# board.net
KiCad netlist of a schematic drawn in EAGLE
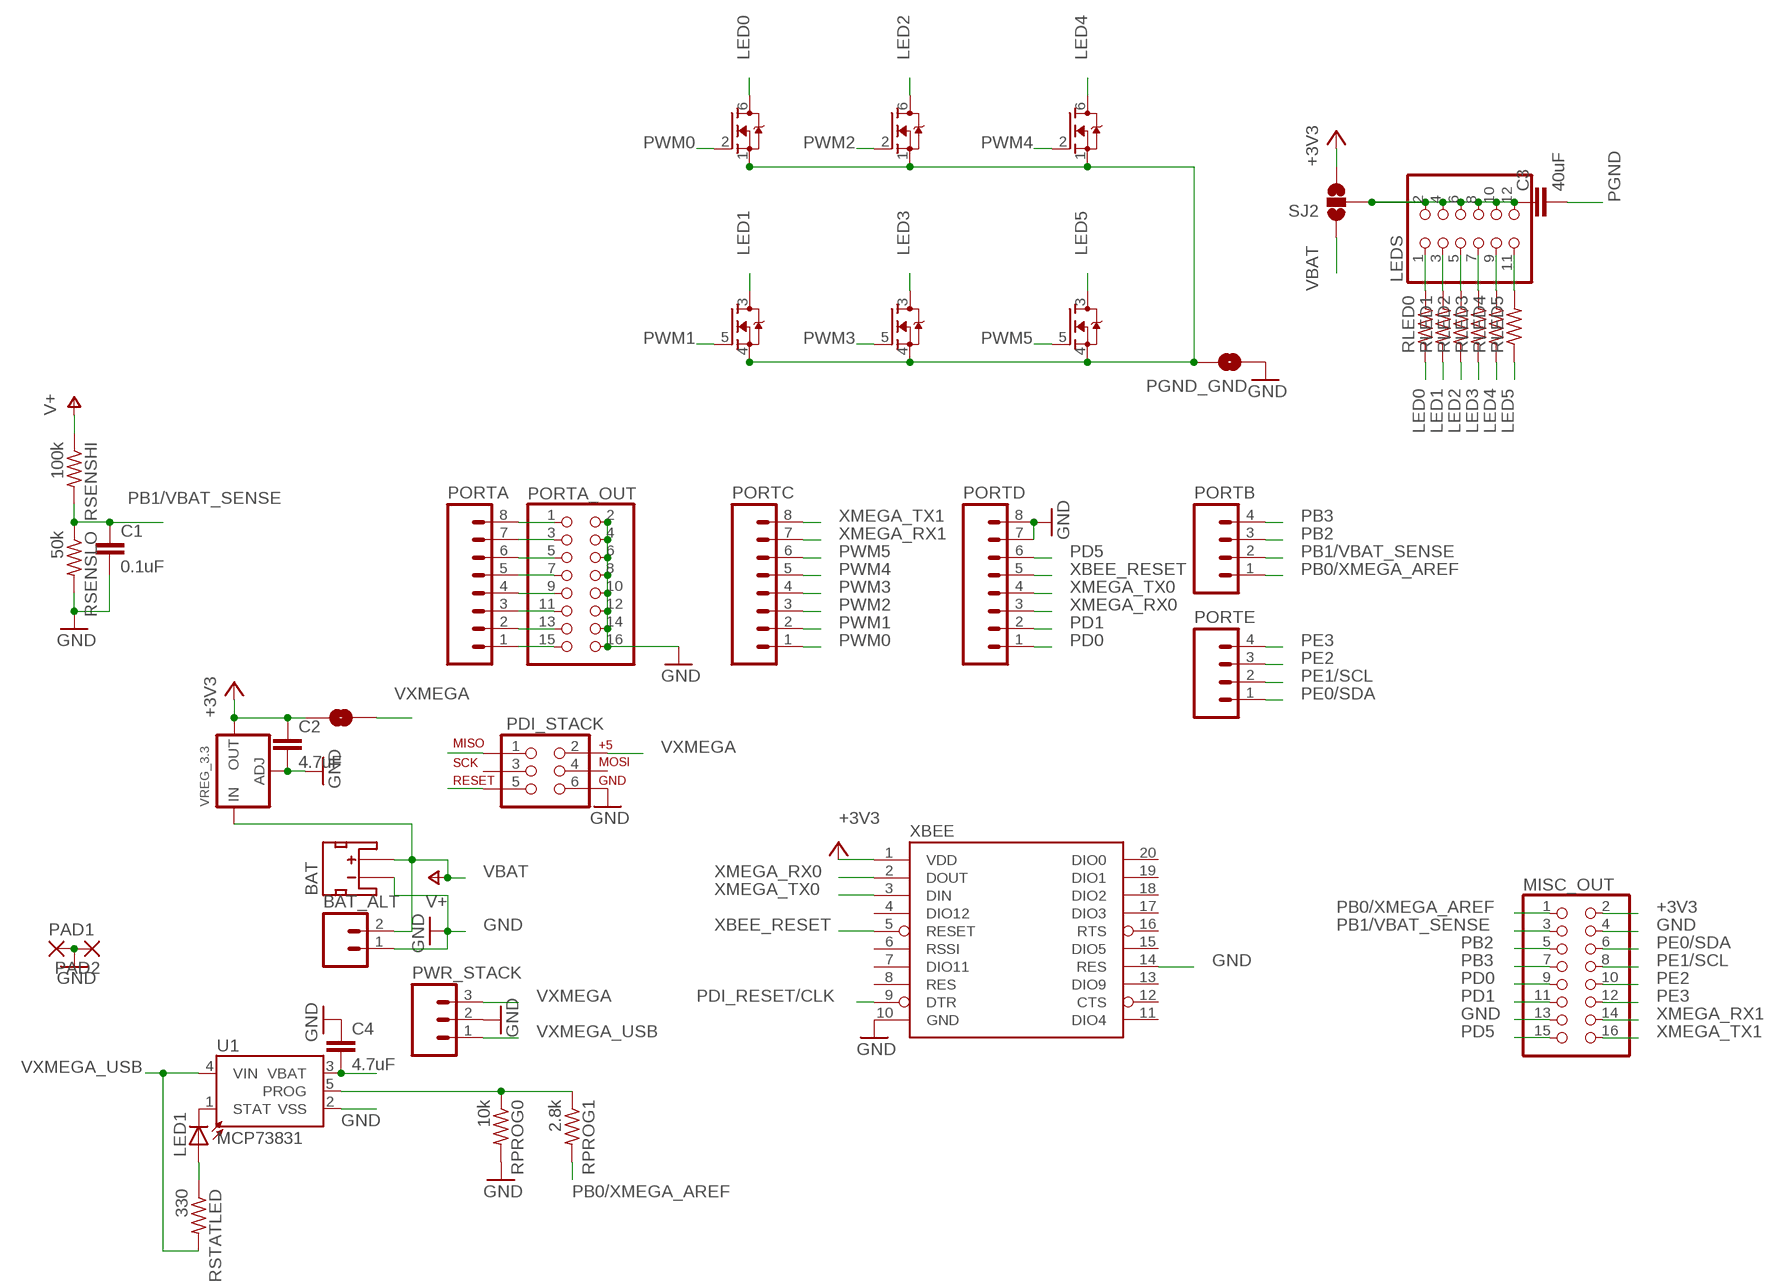
[diagram p0: schematic, sheet 1]

(export (version "E")
  (design (tool "Eeschema 10.0.6"))
  (components
    (comp (ref "+3.3V_VXMEGA")
      (value "SOLDERJUMPERTRACE")
      (footprint "eagle-import:SJ_2S-TRACE")
      (libsource (lib "eagle-import") (part "SOLDERJUMPERTRACE"))
    )
    (comp (ref "BAT")
      (value "JST_2MM_MALE")
      (footprint "eagle-import:JST-2-SMD")
      (libsource (lib "eagle-import") (part "JST_2MM_MALE"))
    )
    (comp (ref "BAT_ALT")
      (value "M02PTH")
      (footprint "eagle-import:1X02")
      (libsource (lib "eagle-import") (part "M02PTH"))
    )
    (comp (ref "C1")
      (value "0.1uF")
      (footprint "eagle-import:C0603K")
      (libsource (lib "eagle-import") (part "C-EUC0603K"))
    )
    (comp (ref "C2")
      (value "4.7uF")
      (footprint "eagle-import:C0805K")
      (libsource (lib "eagle-import") (part "C-EUC0805K"))
    )
    (comp (ref "C3")
      (value "40uF")
      (footprint "eagle-import:C1210")
      (libsource (lib "eagle-import") (part "C-EUC1210"))
    )
    (comp (ref "C4")
      (value "4.7uF")
      (footprint "eagle-import:C0805")
      (libsource (lib "eagle-import") (part "C-EUC0805"))
    )
    (comp (ref "DRV0")
      (value "MOSFET-N_DUAL")
      (footprint "eagle-import:SOT363")
      (libsource (lib "eagle-import") (part "MOSFET-N_DUAL"))
    )
    (comp (ref "DRV1")
      (value "MOSFET-N_DUAL")
      (footprint "eagle-import:SOT363")
      (libsource (lib "eagle-import") (part "MOSFET-N_DUAL"))
    )
    (comp (ref "DRV2")
      (value "MOSFET-N_DUAL")
      (footprint "eagle-import:SOT363")
      (libsource (lib "eagle-import") (part "MOSFET-N_DUAL"))
    )
    (comp (ref "LED1")
      (value "LEDCHIP-LED0603")
      (footprint "eagle-import:CHIP-LED0603")
      (libsource (lib "eagle-import") (part "LEDCHIP-LED0603"))
    )
    (comp (ref "LEDS")
      (value "PINHD-2X6/90")
      (footprint "eagle-import:2X06_90")
      (libsource (lib "eagle-import") (part "PINHD-2X6/90"))
    )
    (comp (ref "MISC_OUT")
      (value "PINHD-2X8/90")
      (footprint "eagle-import:2X08_90")
      (libsource (lib "eagle-import") (part "PINHD-2X8/90"))
    )
    (comp (ref "PAD1")
      (value "3,81/1,4")
      (footprint "eagle-import:3,81_1,4")
      (libsource (lib "eagle-import") (part "3,81/1,4"))
    )
    (comp (ref "PAD2")
      (value "3,81/1,4")
      (footprint "eagle-import:3,81_1,4")
      (libsource (lib "eagle-import") (part "3,81/1,4"))
    )
    (comp (ref "PDI_STACK")
      (value "AVR_SPI_PRG_6NS")
      (footprint "eagle-import:2X3-NS")
      (libsource (lib "eagle-import") (part "AVR_SPI_PRG_6NS"))
    )
    (comp (ref "PGND_GND")
      (value "SOLDERJUMPERTRACE")
      (footprint "eagle-import:SJ_2S-TRACE")
      (libsource (lib "eagle-import") (part "SOLDERJUMPERTRACE"))
    )
    (comp (ref "PORTA")
      (value "M081X08")
      (footprint "eagle-import:1X08")
      (libsource (lib "eagle-import") (part "M081X08"))
    )
    (comp (ref "PORTA_OUT")
      (value "PINHD-2X8")
      (footprint "eagle-import:2X08")
      (libsource (lib "eagle-import") (part "PINHD-2X8"))
    )
    (comp (ref "PORTB")
      (value "M04PTH")
      (footprint "eagle-import:1X04")
      (libsource (lib "eagle-import") (part "M04PTH"))
    )
    (comp (ref "PORTC")
      (value "M081X08")
      (footprint "eagle-import:1X08")
      (libsource (lib "eagle-import") (part "M081X08"))
    )
    (comp (ref "PORTD")
      (value "M081X08")
      (footprint "eagle-import:1X08")
      (libsource (lib "eagle-import") (part "M081X08"))
    )
    (comp (ref "PORTE")
      (value "M04PTH")
      (footprint "eagle-import:1X04")
      (libsource (lib "eagle-import") (part "M04PTH"))
    )
    (comp (ref "PWR_STACK")
      (value "M03PTH")
      (footprint "eagle-import:1X03")
      (libsource (lib "eagle-import") (part "M03PTH"))
    )
    (comp (ref "RLED0")
      (value "R-US_R0805")
      (footprint "eagle-import:R0805")
      (libsource (lib "eagle-import") (part "resistor_R-US_R0805"))
    )
    (comp (ref "RLED1")
      (value "R-US_R0805")
      (footprint "eagle-import:R0805")
      (libsource (lib "eagle-import") (part "resistor_R-US_R0805"))
    )
    (comp (ref "RLED2")
      (value "R-US_R0805")
      (footprint "eagle-import:R0805")
      (libsource (lib "eagle-import") (part "resistor_R-US_R0805"))
    )
    (comp (ref "RLED3")
      (value "R-US_R0805")
      (footprint "eagle-import:R0805")
      (libsource (lib "eagle-import") (part "resistor_R-US_R0805"))
    )
    (comp (ref "RLED4")
      (value "R-US_R0805")
      (footprint "eagle-import:R0805")
      (libsource (lib "eagle-import") (part "resistor_R-US_R0805"))
    )
    (comp (ref "RLED5")
      (value "R-US_R0805")
      (footprint "eagle-import:R0805")
      (libsource (lib "eagle-import") (part "resistor_R-US_R0805"))
    )
    (comp (ref "RPROG0")
      (value "10k")
      (footprint "eagle-import:R0603")
      (libsource (lib "eagle-import") (part "R-US_R0603"))
    )
    (comp (ref "RPROG1")
      (value "2.8k")
      (footprint "eagle-import:R0603")
      (libsource (lib "eagle-import") (part "R-US_R0603"))
    )
    (comp (ref "RSENSHI")
      (value "100k")
      (footprint "eagle-import:R0603")
      (libsource (lib "eagle-import") (part "R-US_R0603"))
    )
    (comp (ref "RSENSLO")
      (value "50k")
      (footprint "eagle-import:R0603")
      (libsource (lib "eagle-import") (part "R-US_R0603"))
    )
    (comp (ref "RSTATLED")
      (value "330")
      (footprint "eagle-import:R0603")
      (libsource (lib "eagle-import") (part "R-US_R0603"))
    )
    (comp (ref "SJ2")
      (value "SOLDERJUMPER_2WAY-OLDT")
      (footprint "eagle-import:SJ_2")
      (libsource (lib "eagle-import") (part "SOLDERJUMPER_2WAY-OLDT"))
    )
    (comp (ref "U1")
      (value "MCP73831")
      (footprint "eagle-import:SOT23-5")
      (libsource (lib "eagle-import") (part "MCP73831"))
    )
    (comp (ref "VREG_3.3")
      (value "LM1117SOT223-WAVE")
      (footprint "eagle-import:SOT223-W")
      (libsource (lib "eagle-import") (part "LM1117SOT223-WAVE"))
    )
    (comp (ref "XBEE")
      (value "XBEE-1B2")
      (footprint "eagle-import:XBEE-SILK")
      (libsource (lib "eagle-import") (part "XBEE-1B2"))
    )
  )
  (nets
    (net (code "1") (name "+3V3") (class "Default")
      (node (ref "+3.3V_VXMEGA") (pin "1") (pinfunction "1_1") (pintype "passive"))
      (node (ref "C2") (pin "1") (pinfunction "1_1") (pintype "passive"))
      (node (ref "MISC_OUT") (pin "2") (pinfunction "2_2") (pintype "passive"))
      (node (ref "SJ2") (pin "3") (pinfunction "3_3") (pintype "passive"))
      (node (ref "VREG_3.3") (pin "2") (pinfunction "OUT_2") (pintype "passive"))
      (node (ref "XBEE") (pin "1") (pinfunction "VDD_1") (pintype "power_in"))
    )
    (net (code "2") (name "/LED0") (class "Default")
      (node (ref "DRV0") (pin "6") (pinfunction "D_6") (pintype "bidirectional"))
      (node (ref "RLED0") (pin "1") (pinfunction "1_1") (pintype "passive"))
    )
    (net (code "3") (name "/LED1") (class "Default")
      (node (ref "DRV0") (pin "3") (pinfunction "D_3") (pintype "bidirectional"))
      (node (ref "RLED1") (pin "1") (pinfunction "1_1") (pintype "passive"))
    )
    (net (code "4") (name "/LED2") (class "Default")
      (node (ref "DRV1") (pin "6") (pinfunction "D_6") (pintype "bidirectional"))
      (node (ref "RLED2") (pin "1") (pinfunction "1_1") (pintype "passive"))
    )
    (net (code "5") (name "/LED3") (class "Default")
      (node (ref "DRV1") (pin "3") (pinfunction "D_3") (pintype "bidirectional"))
      (node (ref "RLED3") (pin "1") (pinfunction "1_1") (pintype "passive"))
    )
    (net (code "6") (name "/LED4") (class "Default")
      (node (ref "DRV2") (pin "6") (pinfunction "D_6") (pintype "bidirectional"))
      (node (ref "RLED4") (pin "1") (pinfunction "1_1") (pintype "passive"))
    )
    (net (code "7") (name "/LED5") (class "Default")
      (node (ref "DRV2") (pin "3") (pinfunction "D_3") (pintype "bidirectional"))
      (node (ref "RLED5") (pin "1") (pinfunction "1_1") (pintype "passive"))
    )
    (net (code "8") (name "/PB0{slash}XMEGA_AREF") (class "Default")
      (node (ref "MISC_OUT") (pin "1") (pinfunction "1_1") (pintype "passive"))
      (node (ref "PORTB") (pin "1") (pinfunction "1_1") (pintype "passive"))
      (node (ref "RPROG1") (pin "2") (pinfunction "2_2") (pintype "passive"))
    )
    (net (code "9") (name "/PB1{slash}VBAT_SENSE") (class "Default")
      (node (ref "C1") (pin "1") (pinfunction "1_1") (pintype "passive"))
      (node (ref "MISC_OUT") (pin "3") (pinfunction "3_3") (pintype "passive"))
      (node (ref "PORTB") (pin "2") (pinfunction "2_2") (pintype "passive"))
      (node (ref "RSENSHI") (pin "2") (pinfunction "2_2") (pintype "passive"))
      (node (ref "RSENSLO") (pin "1") (pinfunction "1_1") (pintype "passive"))
    )
    (net (code "10") (name "/PB2") (class "Default")
      (node (ref "MISC_OUT") (pin "5") (pinfunction "5_5") (pintype "passive"))
      (node (ref "PORTB") (pin "3") (pinfunction "3_3") (pintype "passive"))
    )
    (net (code "11") (name "/PB3") (class "Default")
      (node (ref "MISC_OUT") (pin "7") (pinfunction "7_7") (pintype "passive"))
      (node (ref "PORTB") (pin "4") (pinfunction "4_4") (pintype "passive"))
    )
    (net (code "12") (name "/PD0") (class "Default")
      (node (ref "MISC_OUT") (pin "9") (pinfunction "9_9") (pintype "passive"))
      (node (ref "PORTD") (pin "1") (pinfunction "1_1") (pintype "passive"))
    )
    (net (code "13") (name "/PD1") (class "Default")
      (node (ref "MISC_OUT") (pin "11") (pinfunction "11_11") (pintype "passive"))
      (node (ref "PORTD") (pin "2") (pinfunction "2_2") (pintype "passive"))
    )
    (net (code "14") (name "/PD5") (class "Default")
      (node (ref "MISC_OUT") (pin "15") (pinfunction "15_15") (pintype "passive"))
      (node (ref "PORTD") (pin "6") (pinfunction "6_6") (pintype "passive"))
    )
    (net (code "15") (name "/PDI_RESET{slash}CLK") (class "Default")
      (node (ref "PDI_STACK") (pin "5") (pinfunction "5_5") (pintype "passive"))
      (node (ref "XBEE") (pin "9") (pinfunction "DTR_9") (pintype "bidirectional"))
    )
    (net (code "16") (name "/PE0{slash}SDA") (class "Default")
      (node (ref "MISC_OUT") (pin "6") (pinfunction "6_6") (pintype "passive"))
      (node (ref "PORTE") (pin "1") (pinfunction "1_1") (pintype "passive"))
    )
    (net (code "17") (name "/PE1{slash}SCL") (class "Default")
      (node (ref "MISC_OUT") (pin "8") (pinfunction "8_8") (pintype "passive"))
      (node (ref "PORTE") (pin "2") (pinfunction "2_2") (pintype "passive"))
    )
    (net (code "18") (name "/PE2") (class "Default")
      (node (ref "MISC_OUT") (pin "10") (pinfunction "10_10") (pintype "passive"))
      (node (ref "PORTE") (pin "3") (pinfunction "3_3") (pintype "passive"))
    )
    (net (code "19") (name "/PE3") (class "Default")
      (node (ref "MISC_OUT") (pin "12") (pinfunction "12_12") (pintype "passive"))
      (node (ref "PORTE") (pin "4") (pinfunction "4_4") (pintype "passive"))
    )
    (net (code "20") (name "/PGND") (class "Default")
      (node (ref "C3") (pin "2") (pinfunction "2_2") (pintype "passive"))
      (node (ref "DRV0") (pin "1") (pinfunction "S_1") (pintype "bidirectional"))
      (node (ref "DRV0") (pin "4") (pinfunction "S_4") (pintype "bidirectional"))
      (node (ref "DRV1") (pin "1") (pinfunction "S_1") (pintype "bidirectional"))
      (node (ref "DRV1") (pin "4") (pinfunction "S_4") (pintype "bidirectional"))
      (node (ref "DRV2") (pin "1") (pinfunction "S_1") (pintype "bidirectional"))
      (node (ref "DRV2") (pin "4") (pinfunction "S_4") (pintype "bidirectional"))
      (node (ref "PGND_GND") (pin "2") (pinfunction "2_2") (pintype "passive"))
    )
    (net (code "21") (name "/PWM0") (class "Default")
      (node (ref "DRV0") (pin "2") (pinfunction "G_2") (pintype "bidirectional"))
      (node (ref "PORTC") (pin "1") (pinfunction "1_1") (pintype "passive"))
    )
    (net (code "22") (name "/PWM1") (class "Default")
      (node (ref "DRV0") (pin "5") (pinfunction "G_5") (pintype "bidirectional"))
      (node (ref "PORTC") (pin "2") (pinfunction "2_2") (pintype "passive"))
    )
    (net (code "23") (name "/PWM2") (class "Default")
      (node (ref "DRV1") (pin "2") (pinfunction "G_2") (pintype "bidirectional"))
      (node (ref "PORTC") (pin "3") (pinfunction "3_3") (pintype "passive"))
    )
    (net (code "24") (name "/PWM3") (class "Default")
      (node (ref "DRV1") (pin "5") (pinfunction "G_5") (pintype "bidirectional"))
      (node (ref "PORTC") (pin "4") (pinfunction "4_4") (pintype "passive"))
    )
    (net (code "25") (name "/PWM4") (class "Default")
      (node (ref "DRV2") (pin "2") (pinfunction "G_2") (pintype "bidirectional"))
      (node (ref "PORTC") (pin "5") (pinfunction "5_5") (pintype "passive"))
    )
    (net (code "26") (name "/PWM5") (class "Default")
      (node (ref "DRV2") (pin "5") (pinfunction "G_5") (pintype "bidirectional"))
      (node (ref "PORTC") (pin "6") (pinfunction "6_6") (pintype "passive"))
    )
    (net (code "27") (name "/VXMEGA") (class "Default")
      (node (ref "+3.3V_VXMEGA") (pin "2") (pinfunction "2_2") (pintype "passive"))
      (node (ref "PDI_STACK") (pin "2") (pinfunction "2_2") (pintype "passive"))
      (node (ref "PWR_STACK") (pin "3") (pinfunction "3_3") (pintype "passive"))
    )
    (net (code "28") (name "/VXMEGA_USB") (class "Default")
      (node (ref "PWR_STACK") (pin "1") (pinfunction "1_1") (pintype "passive"))
      (node (ref "RSTATLED") (pin "2") (pinfunction "2_2") (pintype "passive"))
      (node (ref "U1") (pin "4") (pinfunction "VIN_4") (pintype "power_in"))
    )
    (net (code "29") (name "/XBEE_RESET") (class "Default")
      (node (ref "PORTD") (pin "5") (pinfunction "5_5") (pintype "passive"))
      (node (ref "XBEE") (pin "5") (pinfunction "RESET_5") (pintype "input"))
    )
    (net (code "30") (name "/XMEGA_RX0") (class "Default")
      (node (ref "PORTD") (pin "3") (pinfunction "3_3") (pintype "passive"))
      (node (ref "XBEE") (pin "2") (pinfunction "DOUT_2") (pintype "output"))
    )
    (net (code "31") (name "/XMEGA_RX1") (class "Default")
      (node (ref "MISC_OUT") (pin "14") (pinfunction "14_14") (pintype "passive"))
      (node (ref "PORTC") (pin "7") (pinfunction "7_7") (pintype "passive"))
    )
    (net (code "32") (name "/XMEGA_TX0") (class "Default")
      (node (ref "PORTD") (pin "4") (pinfunction "4_4") (pintype "passive"))
      (node (ref "XBEE") (pin "3") (pinfunction "DIN_3") (pintype "input"))
    )
    (net (code "33") (name "/XMEGA_TX1") (class "Default")
      (node (ref "MISC_OUT") (pin "16") (pinfunction "16_16") (pintype "passive"))
      (node (ref "PORTC") (pin "8") (pinfunction "8_8") (pintype "passive"))
    )
    (net (code "34") (name "GND") (class "Default")
      (node (ref "BAT") (pin "1") (pinfunction "-_1") (pintype "bidirectional"))
      (node (ref "BAT_ALT") (pin "1") (pinfunction "1_1") (pintype "passive"))
      (node (ref "C1") (pin "2") (pinfunction "2_2") (pintype "passive"))
      (node (ref "C2") (pin "2") (pinfunction "2_2") (pintype "passive"))
      (node (ref "C4") (pin "1") (pinfunction "1_1") (pintype "passive"))
      (node (ref "MISC_OUT") (pin "13") (pinfunction "13_13") (pintype "passive"))
      (node (ref "MISC_OUT") (pin "4") (pinfunction "4_4") (pintype "passive"))
      (node (ref "PAD1") (pin "1") (pinfunction "P_1") (pintype "passive"))
      (node (ref "PAD2") (pin "1") (pinfunction "P_1") (pintype "passive"))
      (node (ref "PDI_STACK") (pin "6") (pinfunction "6_6") (pintype "passive"))
      (node (ref "PGND_GND") (pin "1") (pinfunction "1_1") (pintype "passive"))
      (node (ref "PORTA_OUT") (pin "10") (pinfunction "10_10") (pintype "passive"))
      (node (ref "PORTA_OUT") (pin "12") (pinfunction "12_12") (pintype "passive"))
      (node (ref "PORTA_OUT") (pin "14") (pinfunction "14_14") (pintype "passive"))
      (node (ref "PORTA_OUT") (pin "16") (pinfunction "16_16") (pintype "passive"))
      (node (ref "PORTA_OUT") (pin "2") (pinfunction "2_2") (pintype "passive"))
      (node (ref "PORTA_OUT") (pin "4") (pinfunction "4_4") (pintype "passive"))
      (node (ref "PORTA_OUT") (pin "6") (pinfunction "6_6") (pintype "passive"))
      (node (ref "PORTA_OUT") (pin "8") (pinfunction "8_8") (pintype "passive"))
      (node (ref "PORTD") (pin "7") (pinfunction "7_7") (pintype "passive"))
      (node (ref "PORTD") (pin "8") (pinfunction "8_8") (pintype "passive"))
      (node (ref "PWR_STACK") (pin "2") (pinfunction "2_2") (pintype "passive"))
      (node (ref "RPROG0") (pin "2") (pinfunction "2_2") (pintype "passive"))
      (node (ref "RSENSLO") (pin "2") (pinfunction "2_2") (pintype "passive"))
      (node (ref "U1") (pin "2") (pinfunction "VSS_2") (pintype "power_in"))
      (node (ref "VREG_3.3") (pin "1") (pinfunction "ADJ_1") (pintype "input"))
      (node (ref "XBEE") (pin "10") (pinfunction "GND_10") (pintype "power_in"))
      (node (ref "XBEE") (pin "14") (pinfunction "RES_14") (pintype "bidirectional"))
    )
    (net (code "35") (name "Net-(C3-Pad1)") (class "Default")
      (node (ref "C3") (pin "1") (pinfunction "1_1") (pintype "passive"))
      (node (ref "LEDS") (pin "10") (pinfunction "10_10") (pintype "passive"))
      (node (ref "LEDS") (pin "12") (pinfunction "12_12") (pintype "passive"))
      (node (ref "LEDS") (pin "2") (pinfunction "2_2") (pintype "passive"))
      (node (ref "LEDS") (pin "4") (pinfunction "4_4") (pintype "passive"))
      (node (ref "LEDS") (pin "6") (pinfunction "6_6") (pintype "passive"))
      (node (ref "LEDS") (pin "8") (pinfunction "8_8") (pintype "passive"))
      (node (ref "SJ2") (pin "2") (pinfunction "2_2") (pintype "passive"))
    )
    (net (code "36") (name "Net-(LED1-PadA)") (class "Default")
      (node (ref "LED1") (pin "A") (pinfunction "A_A") (pintype "passive"))
      (node (ref "RSTATLED") (pin "1") (pinfunction "1_1") (pintype "passive"))
    )
    (net (code "37") (name "Net-(LEDS-Pad1)") (class "Default")
      (node (ref "LEDS") (pin "1") (pinfunction "1_1") (pintype "passive"))
      (node (ref "RLED0") (pin "2") (pinfunction "2_2") (pintype "passive"))
    )
    (net (code "38") (name "Net-(LEDS-Pad3)") (class "Default")
      (node (ref "LEDS") (pin "3") (pinfunction "3_3") (pintype "passive"))
      (node (ref "RLED1") (pin "2") (pinfunction "2_2") (pintype "passive"))
    )
    (net (code "39") (name "Net-(LEDS-Pad5)") (class "Default")
      (node (ref "LEDS") (pin "5") (pinfunction "5_5") (pintype "passive"))
      (node (ref "RLED2") (pin "2") (pinfunction "2_2") (pintype "passive"))
    )
    (net (code "40") (name "Net-(LEDS-Pad7)") (class "Default")
      (node (ref "LEDS") (pin "7") (pinfunction "7_7") (pintype "passive"))
      (node (ref "RLED3") (pin "2") (pinfunction "2_2") (pintype "passive"))
    )
    (net (code "41") (name "Net-(LEDS-Pad9)") (class "Default")
      (node (ref "LEDS") (pin "9") (pinfunction "9_9") (pintype "passive"))
      (node (ref "RLED4") (pin "2") (pinfunction "2_2") (pintype "passive"))
    )
    (net (code "42") (name "Net-(LEDS-Pad11)") (class "Default")
      (node (ref "LEDS") (pin "11") (pinfunction "11_11") (pintype "passive"))
      (node (ref "RLED5") (pin "2") (pinfunction "2_2") (pintype "passive"))
    )
    (net (code "43") (name "Net-(PORTA-Pad1)") (class "Default")
      (node (ref "PORTA") (pin "1") (pinfunction "1_1") (pintype "passive"))
      (node (ref "PORTA_OUT") (pin "15") (pinfunction "15_15") (pintype "passive"))
    )
    (net (code "44") (name "Net-(PORTA-Pad2)") (class "Default")
      (node (ref "PORTA") (pin "2") (pinfunction "2_2") (pintype "passive"))
      (node (ref "PORTA_OUT") (pin "13") (pinfunction "13_13") (pintype "passive"))
    )
    (net (code "45") (name "Net-(PORTA-Pad3)") (class "Default")
      (node (ref "PORTA") (pin "3") (pinfunction "3_3") (pintype "passive"))
      (node (ref "PORTA_OUT") (pin "11") (pinfunction "11_11") (pintype "passive"))
    )
    (net (code "46") (name "Net-(PORTA-Pad4)") (class "Default")
      (node (ref "PORTA") (pin "4") (pinfunction "4_4") (pintype "passive"))
      (node (ref "PORTA_OUT") (pin "9") (pinfunction "9_9") (pintype "passive"))
    )
    (net (code "47") (name "Net-(PORTA-Pad5)") (class "Default")
      (node (ref "PORTA") (pin "5") (pinfunction "5_5") (pintype "passive"))
      (node (ref "PORTA_OUT") (pin "7") (pinfunction "7_7") (pintype "passive"))
    )
    (net (code "48") (name "Net-(PORTA-Pad6)") (class "Default")
      (node (ref "PORTA") (pin "6") (pinfunction "6_6") (pintype "passive"))
      (node (ref "PORTA_OUT") (pin "5") (pinfunction "5_5") (pintype "passive"))
    )
    (net (code "49") (name "Net-(PORTA-Pad7)") (class "Default")
      (node (ref "PORTA") (pin "7") (pinfunction "7_7") (pintype "passive"))
      (node (ref "PORTA_OUT") (pin "3") (pinfunction "3_3") (pintype "passive"))
    )
    (net (code "50") (name "Net-(PORTA-Pad8)") (class "Default")
      (node (ref "PORTA") (pin "8") (pinfunction "8_8") (pintype "passive"))
      (node (ref "PORTA_OUT") (pin "1") (pinfunction "1_1") (pintype "passive"))
    )
    (net (code "51") (name "Net-(U1-PROG)") (class "Default")
      (node (ref "RPROG0") (pin "1") (pinfunction "1_1") (pintype "passive"))
      (node (ref "RPROG1") (pin "1") (pinfunction "1_1") (pintype "passive"))
      (node (ref "U1") (pin "5") (pinfunction "PROG_5") (pintype "input"))
    )
    (net (code "52") (name "Net-(U1-STAT)") (class "Default")
      (node (ref "LED1") (pin "C") (pinfunction "C_C") (pintype "passive"))
      (node (ref "U1") (pin "1") (pinfunction "STAT_1") (pintype "output"))
    )
    (net (code "53") (name "V+") (class "Default")
      (node (ref "BAT") (pin "2") (pinfunction "+_2") (pintype "bidirectional"))
      (node (ref "BAT_ALT") (pin "2") (pinfunction "2_2") (pintype "passive"))
      (node (ref "C4") (pin "2") (pinfunction "2_2") (pintype "passive"))
      (node (ref "RSENSHI") (pin "1") (pinfunction "1_1") (pintype "passive"))
      (node (ref "SJ2") (pin "1") (pinfunction "1_1") (pintype "passive"))
      (node (ref "U1") (pin "3") (pinfunction "VBAT_3") (pintype "power_in"))
      (node (ref "VREG_3.3") (pin "3") (pinfunction "IN_3") (pintype "input"))
    )
    (net (code "54") (name "unconnected-(BAT-PAD1-PadNC1)") (class "Default")
      (node (ref "BAT") (pin "NC1") (pinfunction "PAD1_NC1") (pintype "bidirectional"))
    )
    (net (code "55") (name "unconnected-(BAT-PAD2-PadNC2)") (class "Default")
      (node (ref "BAT") (pin "NC2") (pinfunction "PAD2_NC2") (pintype "bidirectional"))
    )
    (net (code "56") (name "unconnected-(PDI_STACK-Pad1)") (class "Default")
      (node (ref "PDI_STACK") (pin "1") (pinfunction "1_1") (pintype "passive"))
    )
    (net (code "57") (name "unconnected-(PDI_STACK-Pad3)") (class "Default")
      (node (ref "PDI_STACK") (pin "3") (pinfunction "3_3") (pintype "passive"))
    )
    (net (code "58") (name "unconnected-(PDI_STACK-Pad4)") (class "Default")
      (node (ref "PDI_STACK") (pin "4") (pinfunction "4_4") (pintype "passive"))
    )
    (net (code "59") (name "unconnected-(XBEE-CTS-Pad12)") (class "Default")
      (node (ref "XBEE") (pin "12") (pinfunction "CTS_12") (pintype "output"))
    )
    (net (code "60") (name "unconnected-(XBEE-DIO0-Pad20)") (class "Default")
      (node (ref "XBEE") (pin "20") (pinfunction "DIO0_20") (pintype "bidirectional"))
    )
    (net (code "61") (name "unconnected-(XBEE-DIO1-Pad19)") (class "Default")
      (node (ref "XBEE") (pin "19") (pinfunction "DIO1_19") (pintype "bidirectional"))
    )
    (net (code "62") (name "unconnected-(XBEE-DIO2-Pad18)") (class "Default")
      (node (ref "XBEE") (pin "18") (pinfunction "DIO2_18") (pintype "bidirectional"))
    )
    (net (code "63") (name "unconnected-(XBEE-DIO3-Pad17)") (class "Default")
      (node (ref "XBEE") (pin "17") (pinfunction "DIO3_17") (pintype "bidirectional"))
    )
    (net (code "64") (name "unconnected-(XBEE-DIO4-Pad11)") (class "Default")
      (node (ref "XBEE") (pin "11") (pinfunction "DIO4_11") (pintype "bidirectional"))
    )
    (net (code "65") (name "unconnected-(XBEE-DIO5-Pad15)") (class "Default")
      (node (ref "XBEE") (pin "15") (pinfunction "DIO5_15") (pintype "bidirectional"))
    )
    (net (code "66") (name "unconnected-(XBEE-DIO9-Pad13)") (class "Default")
      (node (ref "XBEE") (pin "13") (pinfunction "DIO9_13") (pintype "bidirectional"))
    )
    (net (code "67") (name "unconnected-(XBEE-DIO11-Pad7)") (class "Default")
      (node (ref "XBEE") (pin "7") (pinfunction "DIO11_7") (pintype "bidirectional"))
    )
    (net (code "68") (name "unconnected-(XBEE-DIO12-Pad4)") (class "Default")
      (node (ref "XBEE") (pin "4") (pinfunction "DIO12_4") (pintype "bidirectional"))
    )
    (net (code "69") (name "unconnected-(XBEE-RES-Pad8)") (class "Default")
      (node (ref "XBEE") (pin "8") (pinfunction "RES_8") (pintype "bidirectional"))
    )
    (net (code "70") (name "unconnected-(XBEE-RSSI-Pad6)") (class "Default")
      (node (ref "XBEE") (pin "6") (pinfunction "RSSI_6") (pintype "bidirectional"))
    )
    (net (code "71") (name "unconnected-(XBEE-RTS-Pad16)") (class "Default")
      (node (ref "XBEE") (pin "16") (pinfunction "RTS_16") (pintype "input"))
    )
  )
)
